# power-distro-board.net
KiCad netlist of a schematic drawn in EAGLE
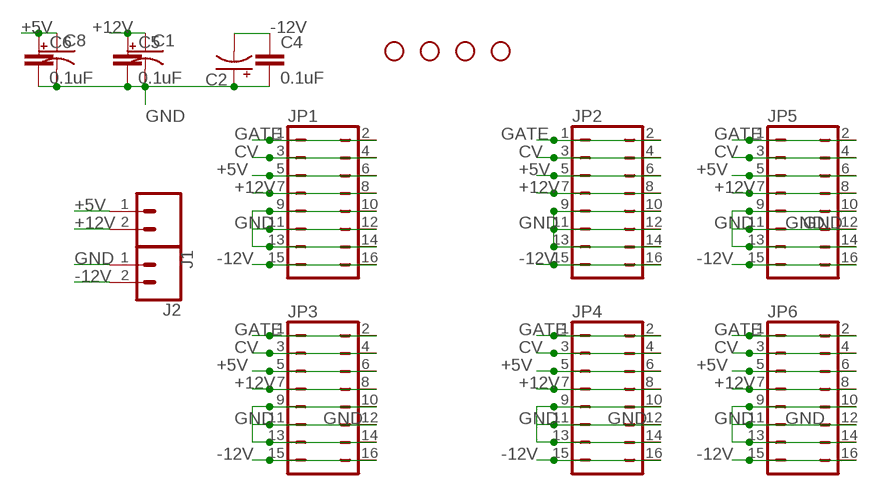
[diagram p0: schematic, sheet 1]

(export (version "E")
  (design (tool "Eeschema 10.0.6"))
  (components
    (comp (ref "C1")
      (value "CPOL-USE2.5-6")
      (footprint "eagle-import:E2,5-6")
      (libsource (lib "eagle-import") (part "CPOL-USE2.5-6"))
    )
    (comp (ref "C2")
      (value "CPOL-USE2.5-6")
      (footprint "eagle-import:E2,5-6")
      (libsource (lib "eagle-import") (part "CPOL-USE2.5-6"))
    )
    (comp (ref "C4")
      (value "0.1uF")
      (footprint "eagle-import:CAP-PTH-SMALL-KIT")
      (libsource (lib "eagle-import") (part "0.1UF-KIT-EZ-50V-20%"))
    )
    (comp (ref "C5")
      (value "0.1uF")
      (footprint "eagle-import:CAP-PTH-SMALL-KIT")
      (libsource (lib "eagle-import") (part "0.1UF-KIT-EZ-50V-20%"))
    )
    (comp (ref "C6")
      (value "0.1uF")
      (footprint "eagle-import:CAP-PTH-SMALL-KIT")
      (libsource (lib "eagle-import") (part "0.1UF-KIT-EZ-50V-20%"))
    )
    (comp (ref "C8")
      (value "CPOL-USE2.5-6")
      (footprint "eagle-import:E2,5-6")
      (libsource (lib "eagle-import") (part "CPOL-USE2.5-6"))
    )
    (comp (ref "H1")
      (value "STAND-OFF")
      (footprint "eagle-import:STAND-OFF")
      (libsource (lib "eagle-import") (part "STAND-OFF"))
    )
    (comp (ref "H2")
      (value "STAND-OFF")
      (footprint "eagle-import:STAND-OFF")
      (libsource (lib "eagle-import") (part "STAND-OFF"))
    )
    (comp (ref "H3")
      (value "STAND-OFF")
      (footprint "eagle-import:STAND-OFF")
      (libsource (lib "eagle-import") (part "STAND-OFF"))
    )
    (comp (ref "H4")
      (value "STAND-OFF")
      (footprint "eagle-import:STAND-OFF")
      (libsource (lib "eagle-import") (part "STAND-OFF"))
    )
    (comp (ref "J1")
      (value "CONN_023.5MM")
      (footprint "eagle-import:SCREWTERMINAL-3.5MM-2")
      (libsource (lib "eagle-import") (part "CONN_023.5MM"))
    )
    (comp (ref "J2")
      (value "CONN_023.5MM")
      (footprint "eagle-import:SCREWTERMINAL-3.5MM-2")
      (libsource (lib "eagle-import") (part "CONN_023.5MM"))
    )
    (comp (ref "JP1")
      (value "JP8Q")
      (footprint "eagle-import:JP8Q")
      (libsource (lib "eagle-import") (part "JP8Q"))
    )
    (comp (ref "JP2")
      (value "JP8Q")
      (footprint "eagle-import:JP8Q")
      (libsource (lib "eagle-import") (part "JP8Q"))
    )
    (comp (ref "JP3")
      (value "JP8Q")
      (footprint "eagle-import:JP8Q")
      (libsource (lib "eagle-import") (part "JP8Q"))
    )
    (comp (ref "JP4")
      (value "JP8Q")
      (footprint "eagle-import:JP8Q")
      (libsource (lib "eagle-import") (part "JP8Q"))
    )
    (comp (ref "JP5")
      (value "JP8Q")
      (footprint "eagle-import:JP8Q")
      (libsource (lib "eagle-import") (part "JP8Q"))
    )
    (comp (ref "JP6")
      (value "JP8Q")
      (footprint "eagle-import:JP8Q")
      (libsource (lib "eagle-import") (part "JP8Q"))
    )
  )
  (nets
    (net (code "1") (name "/+5V") (class "Default")
      (node (ref "C6") (pin "1") (pinfunction "1_1") (pintype "passive"))
      (node (ref "C8") (pin "+") (pinfunction "+_+") (pintype "passive"))
      (node (ref "J1") (pin "1") (pinfunction "1_1") (pintype "passive"))
      (node (ref "JP1") (pin "5") (pinfunction "5_5") (pintype "passive"))
      (node (ref "JP1") (pin "6") (pinfunction "6_6") (pintype "passive"))
      (node (ref "JP2") (pin "5") (pinfunction "5_5") (pintype "passive"))
      (node (ref "JP2") (pin "6") (pinfunction "6_6") (pintype "passive"))
      (node (ref "JP3") (pin "5") (pinfunction "5_5") (pintype "passive"))
      (node (ref "JP3") (pin "6") (pinfunction "6_6") (pintype "passive"))
      (node (ref "JP4") (pin "5") (pinfunction "5_5") (pintype "passive"))
      (node (ref "JP4") (pin "6") (pinfunction "6_6") (pintype "passive"))
      (node (ref "JP5") (pin "5") (pinfunction "5_5") (pintype "passive"))
      (node (ref "JP5") (pin "6") (pinfunction "6_6") (pintype "passive"))
      (node (ref "JP6") (pin "5") (pinfunction "5_5") (pintype "passive"))
      (node (ref "JP6") (pin "6") (pinfunction "6_6") (pintype "passive"))
    )
    (net (code "2") (name "/+12V") (class "Default")
      (node (ref "C1") (pin "+") (pinfunction "+_+") (pintype "passive"))
      (node (ref "C5") (pin "1") (pinfunction "1_1") (pintype "passive"))
      (node (ref "J1") (pin "2") (pinfunction "2_2") (pintype "passive"))
      (node (ref "JP1") (pin "7") (pinfunction "7_7") (pintype "passive"))
      (node (ref "JP1") (pin "8") (pinfunction "8_8") (pintype "passive"))
      (node (ref "JP2") (pin "7") (pinfunction "7_7") (pintype "passive"))
      (node (ref "JP2") (pin "8") (pinfunction "8_8") (pintype "passive"))
      (node (ref "JP3") (pin "7") (pinfunction "7_7") (pintype "passive"))
      (node (ref "JP3") (pin "8") (pinfunction "8_8") (pintype "passive"))
      (node (ref "JP4") (pin "7") (pinfunction "7_7") (pintype "passive"))
      (node (ref "JP4") (pin "8") (pinfunction "8_8") (pintype "passive"))
      (node (ref "JP5") (pin "7") (pinfunction "7_7") (pintype "passive"))
      (node (ref "JP5") (pin "8") (pinfunction "8_8") (pintype "passive"))
      (node (ref "JP6") (pin "7") (pinfunction "7_7") (pintype "passive"))
      (node (ref "JP6") (pin "8") (pinfunction "8_8") (pintype "passive"))
    )
    (net (code "3") (name "/-12V") (class "Default")
      (node (ref "C2") (pin "-") (pinfunction "-_-") (pintype "passive"))
      (node (ref "C4") (pin "1") (pinfunction "1_1") (pintype "passive"))
      (node (ref "J2") (pin "2") (pinfunction "2_2") (pintype "passive"))
      (node (ref "JP1") (pin "15") (pinfunction "15_15") (pintype "passive"))
      (node (ref "JP1") (pin "16") (pinfunction "16_16") (pintype "passive"))
      (node (ref "JP2") (pin "15") (pinfunction "15_15") (pintype "passive"))
      (node (ref "JP2") (pin "16") (pinfunction "16_16") (pintype "passive"))
      (node (ref "JP3") (pin "15") (pinfunction "15_15") (pintype "passive"))
      (node (ref "JP3") (pin "16") (pinfunction "16_16") (pintype "passive"))
      (node (ref "JP4") (pin "15") (pinfunction "15_15") (pintype "passive"))
      (node (ref "JP4") (pin "16") (pinfunction "16_16") (pintype "passive"))
      (node (ref "JP5") (pin "15") (pinfunction "15_15") (pintype "passive"))
      (node (ref "JP5") (pin "16") (pinfunction "16_16") (pintype "passive"))
      (node (ref "JP6") (pin "15") (pinfunction "15_15") (pintype "passive"))
      (node (ref "JP6") (pin "16") (pinfunction "16_16") (pintype "passive"))
    )
    (net (code "4") (name "/CV") (class "Default")
      (node (ref "JP1") (pin "3") (pinfunction "3_3") (pintype "passive"))
      (node (ref "JP1") (pin "4") (pinfunction "4_4") (pintype "passive"))
      (node (ref "JP2") (pin "3") (pinfunction "3_3") (pintype "passive"))
      (node (ref "JP2") (pin "4") (pinfunction "4_4") (pintype "passive"))
      (node (ref "JP3") (pin "3") (pinfunction "3_3") (pintype "passive"))
      (node (ref "JP3") (pin "4") (pinfunction "4_4") (pintype "passive"))
      (node (ref "JP4") (pin "3") (pinfunction "3_3") (pintype "passive"))
      (node (ref "JP4") (pin "4") (pinfunction "4_4") (pintype "passive"))
      (node (ref "JP5") (pin "3") (pinfunction "3_3") (pintype "passive"))
      (node (ref "JP5") (pin "4") (pinfunction "4_4") (pintype "passive"))
      (node (ref "JP6") (pin "3") (pinfunction "3_3") (pintype "passive"))
      (node (ref "JP6") (pin "4") (pinfunction "4_4") (pintype "passive"))
    )
    (net (code "5") (name "/GATE") (class "Default")
      (node (ref "JP1") (pin "1") (pinfunction "1_1") (pintype "passive"))
      (node (ref "JP1") (pin "2") (pinfunction "2_2") (pintype "passive"))
      (node (ref "JP2") (pin "1") (pinfunction "1_1") (pintype "passive"))
      (node (ref "JP2") (pin "2") (pinfunction "2_2") (pintype "passive"))
      (node (ref "JP3") (pin "1") (pinfunction "1_1") (pintype "passive"))
      (node (ref "JP3") (pin "2") (pinfunction "2_2") (pintype "passive"))
      (node (ref "JP4") (pin "1") (pinfunction "1_1") (pintype "passive"))
      (node (ref "JP4") (pin "2") (pinfunction "2_2") (pintype "passive"))
      (node (ref "JP5") (pin "1") (pinfunction "1_1") (pintype "passive"))
      (node (ref "JP5") (pin "2") (pinfunction "2_2") (pintype "passive"))
      (node (ref "JP6") (pin "1") (pinfunction "1_1") (pintype "passive"))
      (node (ref "JP6") (pin "2") (pinfunction "2_2") (pintype "passive"))
    )
    (net (code "6") (name "/GND") (class "Default")
      (node (ref "C1") (pin "-") (pinfunction "-_-") (pintype "passive"))
      (node (ref "C2") (pin "+") (pinfunction "+_+") (pintype "passive"))
      (node (ref "C4") (pin "2") (pinfunction "2_2") (pintype "passive"))
      (node (ref "C5") (pin "2") (pinfunction "2_2") (pintype "passive"))
      (node (ref "C6") (pin "2") (pinfunction "2_2") (pintype "passive"))
      (node (ref "C8") (pin "-") (pinfunction "-_-") (pintype "passive"))
      (node (ref "J2") (pin "1") (pinfunction "1_1") (pintype "passive"))
      (node (ref "JP1") (pin "10") (pinfunction "10_10") (pintype "passive"))
      (node (ref "JP1") (pin "11") (pinfunction "11_11") (pintype "passive"))
      (node (ref "JP1") (pin "12") (pinfunction "12_12") (pintype "passive"))
      (node (ref "JP1") (pin "13") (pinfunction "13_13") (pintype "passive"))
      (node (ref "JP1") (pin "14") (pinfunction "14_14") (pintype "passive"))
      (node (ref "JP1") (pin "9") (pinfunction "9_9") (pintype "passive"))
      (node (ref "JP2") (pin "10") (pinfunction "10_10") (pintype "passive"))
      (node (ref "JP2") (pin "11") (pinfunction "11_11") (pintype "passive"))
      (node (ref "JP2") (pin "12") (pinfunction "12_12") (pintype "passive"))
      (node (ref "JP2") (pin "13") (pinfunction "13_13") (pintype "passive"))
      (node (ref "JP2") (pin "14") (pinfunction "14_14") (pintype "passive"))
      (node (ref "JP2") (pin "9") (pinfunction "9_9") (pintype "passive"))
      (node (ref "JP3") (pin "10") (pinfunction "10_10") (pintype "passive"))
      (node (ref "JP3") (pin "11") (pinfunction "11_11") (pintype "passive"))
      (node (ref "JP3") (pin "12") (pinfunction "12_12") (pintype "passive"))
      (node (ref "JP3") (pin "13") (pinfunction "13_13") (pintype "passive"))
      (node (ref "JP3") (pin "14") (pinfunction "14_14") (pintype "passive"))
      (node (ref "JP3") (pin "9") (pinfunction "9_9") (pintype "passive"))
      (node (ref "JP4") (pin "10") (pinfunction "10_10") (pintype "passive"))
      (node (ref "JP4") (pin "11") (pinfunction "11_11") (pintype "passive"))
      (node (ref "JP4") (pin "12") (pinfunction "12_12") (pintype "passive"))
      (node (ref "JP4") (pin "13") (pinfunction "13_13") (pintype "passive"))
      (node (ref "JP4") (pin "14") (pinfunction "14_14") (pintype "passive"))
      (node (ref "JP4") (pin "9") (pinfunction "9_9") (pintype "passive"))
      (node (ref "JP5") (pin "10") (pinfunction "10_10") (pintype "passive"))
      (node (ref "JP5") (pin "11") (pinfunction "11_11") (pintype "passive"))
      (node (ref "JP5") (pin "12") (pinfunction "12_12") (pintype "passive"))
      (node (ref "JP5") (pin "13") (pinfunction "13_13") (pintype "passive"))
      (node (ref "JP5") (pin "14") (pinfunction "14_14") (pintype "passive"))
      (node (ref "JP5") (pin "9") (pinfunction "9_9") (pintype "passive"))
      (node (ref "JP6") (pin "10") (pinfunction "10_10") (pintype "passive"))
      (node (ref "JP6") (pin "11") (pinfunction "11_11") (pintype "passive"))
      (node (ref "JP6") (pin "12") (pinfunction "12_12") (pintype "passive"))
      (node (ref "JP6") (pin "13") (pinfunction "13_13") (pintype "passive"))
      (node (ref "JP6") (pin "14") (pinfunction "14_14") (pintype "passive"))
      (node (ref "JP6") (pin "9") (pinfunction "9_9") (pintype "passive"))
    )
  )
)
